# Debug-Edge_SWD-to-J-Link-Edu-Mini-adapte.net
KiCad netlist of a schematic drawn in EAGLE
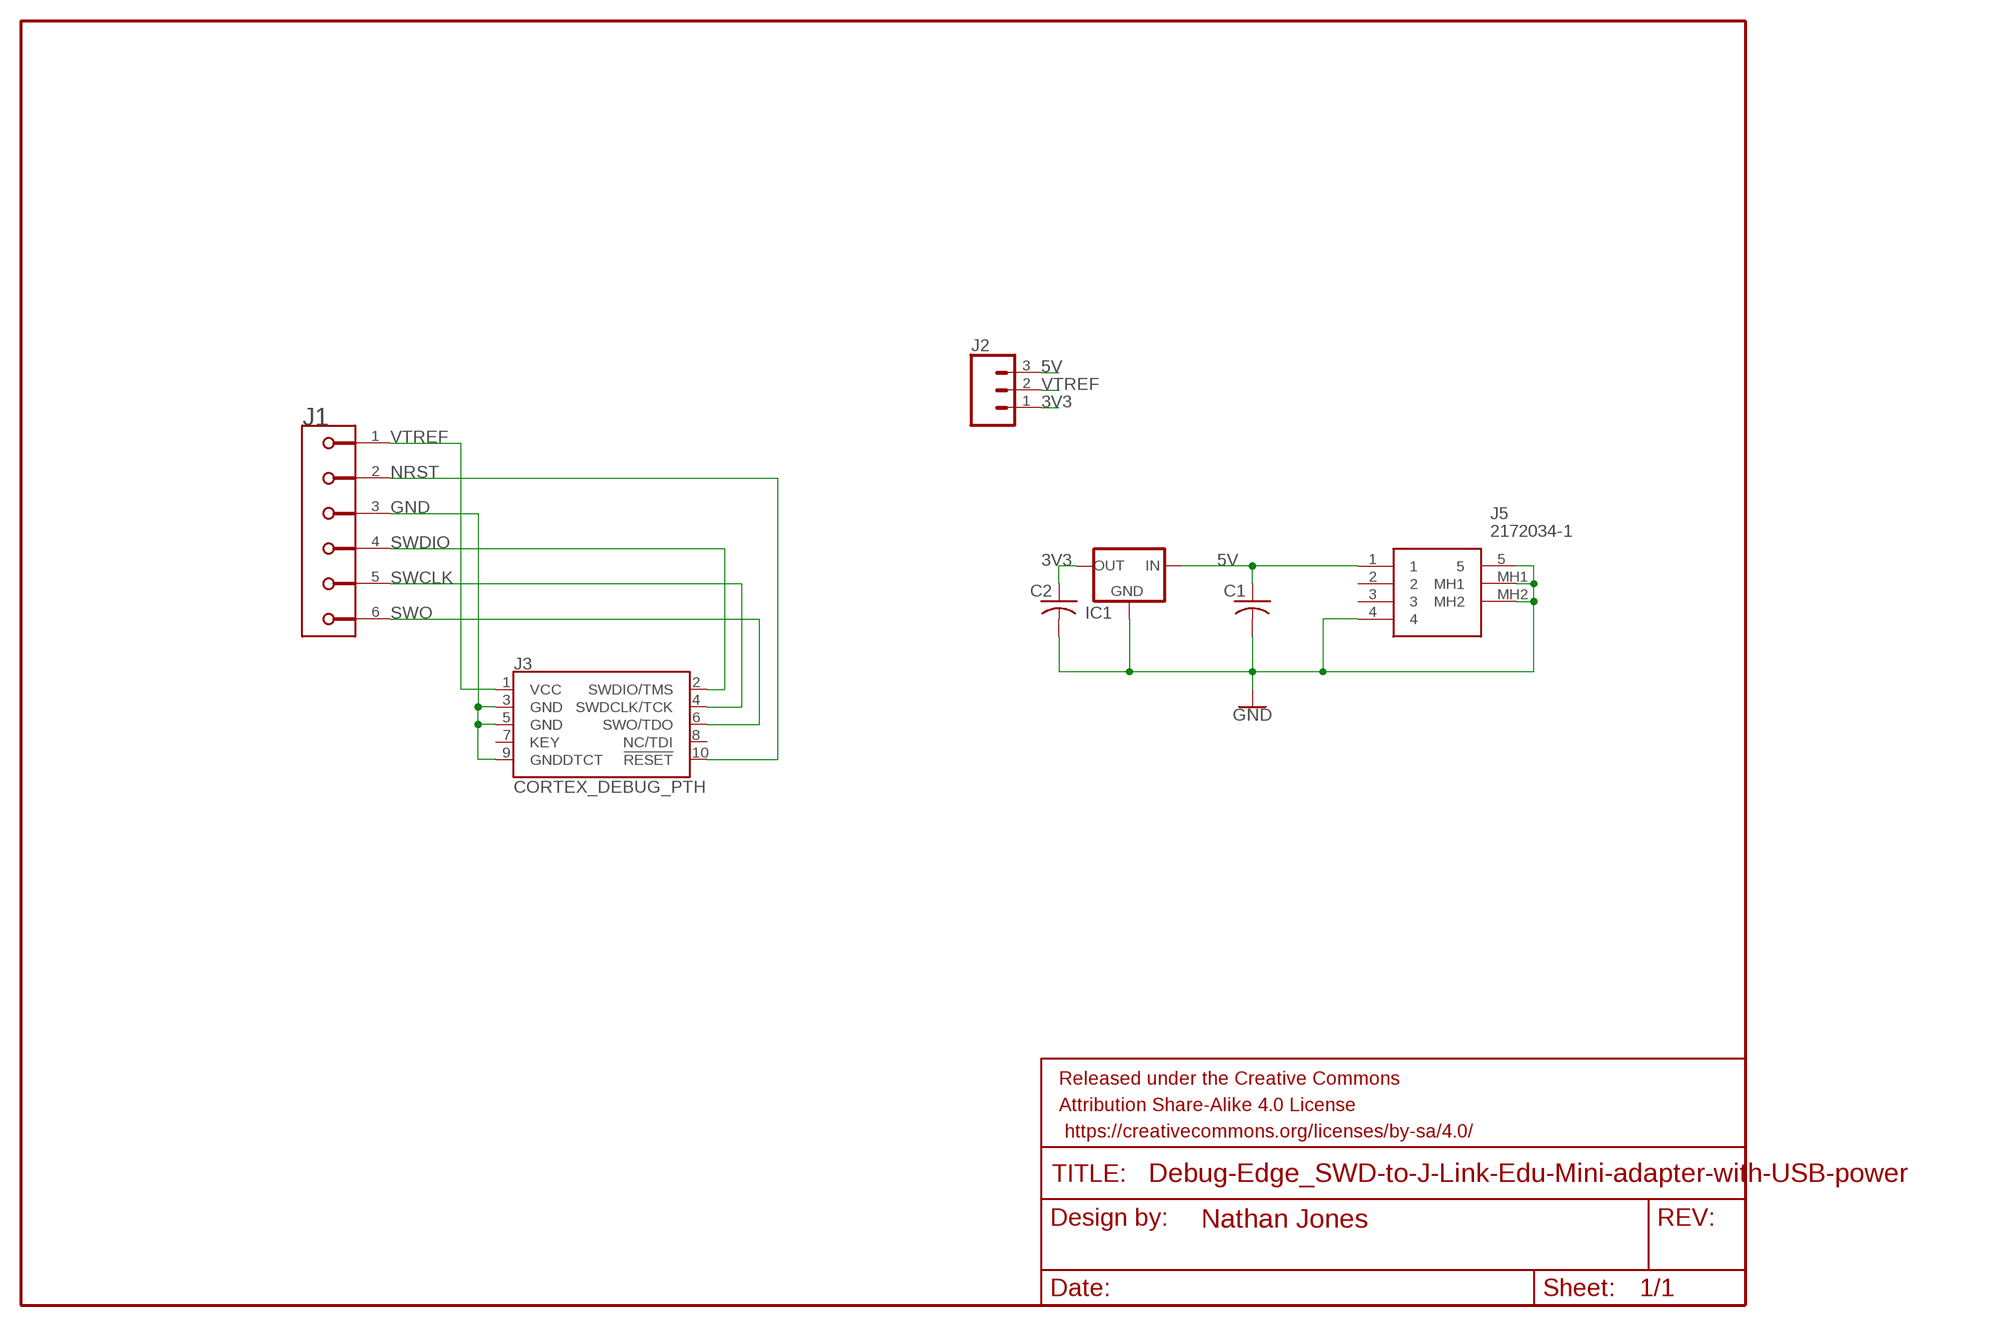
[diagram p0: schematic, sheet 1]

(export (version "E")
  (design (tool "Eeschema 10.0.6"))
  (components
    (comp (ref "C1")
      (value "C-US025-024X044")
      (footprint "eagle-import:C025-024X044")
      (libsource (lib "eagle-import") (part "C-US025-024X044"))
    )
    (comp (ref "C2")
      (value "C-US025-024X044")
      (footprint "eagle-import:C025-024X044")
      (libsource (lib "eagle-import") (part "C-US025-024X044"))
    )
    (comp (ref "FRAME1")
      (value "FRAME-LETTERNO_PACKAGE")
      (footprint "eagle-import:DUMMY")
      (fields (field (name "DESIGNER") "Nathan Jones") (field (name "DESIGNER_1") "Nathan Jones"))
      (libsource (lib "eagle-import") (part "FRAME-LETTERNO_PACKAGE"))
    )
    (comp (ref "IC1")
      (value "MCP1700INLINE")
      (footprint "eagle-import:TO92-INLINE")
      (libsource (lib "eagle-import") (part "MCP1700INLINE"))
    )
    (comp (ref "J1")
      (value "AVX_6-PIN_009159006061916")
      (footprint "eagle-import:AVX_6-PIN_009159006061916_0")
      (libsource (lib "eagle-import") (part "AVX_6-PIN_009159006061916"))
    )
    (comp (ref "J2")
      (value "CONN_031X03_NO_SILK")
      (footprint "eagle-import:1X03_NO_SILK")
      (libsource (lib "eagle-import") (part "CONN_031X03_NO_SILK"))
    )
    (comp (ref "J3")
      (value "CORTEX_DEBUG_PTH")
      (footprint "eagle-import:2X5-PTH-1.27MM")
      (libsource (lib "eagle-import") (part "CORTEX_DEBUG_PTH"))
    )
    (comp (ref "J5")
      (value "2172034-1")
      (footprint "eagle-import:21720341")
      (fields (field (name "MOUSER_PART_NUMBER") "571-2172034-1"))
      (libsource (lib "eagle-import") (part "2172034-1"))
    )
  )
  (nets
    (net (code "1") (name "/3V3") (class "Default")
      (node (ref "C2") (pin "1") (pinfunction "1_1") (pintype "passive"))
      (node (ref "IC1") (pin "3") (pinfunction "OUT_3") (pintype "passive"))
      (node (ref "J2") (pin "1") (pinfunction "1_1") (pintype "passive"))
    )
    (net (code "2") (name "/5V") (class "Default")
      (node (ref "C1") (pin "1") (pinfunction "1_1") (pintype "passive"))
      (node (ref "IC1") (pin "2") (pinfunction "IN_2") (pintype "input"))
      (node (ref "J2") (pin "3") (pinfunction "3_3") (pintype "passive"))
      (node (ref "J5") (pin "1") (pinfunction "1_1") (pintype "bidirectional"))
    )
    (net (code "3") (name "/NRST") (class "Default")
      (node (ref "J1") (pin "2") (pinfunction "2_2") (pintype "bidirectional"))
      (node (ref "J3") (pin "10") (pinfunction "~{RESET}_10") (pintype "bidirectional"))
    )
    (net (code "4") (name "/SWCLK") (class "Default")
      (node (ref "J1") (pin "5") (pinfunction "5_5") (pintype "bidirectional"))
      (node (ref "J3") (pin "4") (pinfunction "SWDCLK/TCK_4") (pintype "bidirectional"))
    )
    (net (code "5") (name "/SWDIO") (class "Default")
      (node (ref "J1") (pin "4") (pinfunction "4_4") (pintype "bidirectional"))
      (node (ref "J3") (pin "2") (pinfunction "SWDIO/TMS_2") (pintype "bidirectional"))
    )
    (net (code "6") (name "/SWO") (class "Default")
      (node (ref "J1") (pin "6") (pinfunction "6_6") (pintype "bidirectional"))
      (node (ref "J3") (pin "6") (pinfunction "SWO/TDO_6") (pintype "bidirectional"))
    )
    (net (code "7") (name "/VTREF") (class "Default")
      (node (ref "J1") (pin "1") (pinfunction "1_1") (pintype "bidirectional"))
      (node (ref "J2") (pin "2") (pinfunction "2_2") (pintype "passive"))
      (node (ref "J3") (pin "1") (pinfunction "VCC_1") (pintype "bidirectional"))
    )
    (net (code "8") (name "GND") (class "Default")
      (node (ref "C1") (pin "2") (pinfunction "2_2") (pintype "passive"))
      (node (ref "C2") (pin "2") (pinfunction "2_2") (pintype "passive"))
      (node (ref "IC1") (pin "1") (pinfunction "GND_1") (pintype "input"))
      (node (ref "J1") (pin "3") (pinfunction "3_3") (pintype "bidirectional"))
      (node (ref "J3") (pin "3") (pinfunction "GND_3") (pintype "bidirectional"))
      (node (ref "J3") (pin "5") (pinfunction "GND_5") (pintype "bidirectional"))
      (node (ref "J3") (pin "9") (pinfunction "GNDDTCT_9") (pintype "bidirectional"))
      (node (ref "J5") (pin "4") (pinfunction "4_4") (pintype "bidirectional"))
      (node (ref "J5") (pin "5") (pinfunction "5_5") (pintype "bidirectional"))
      (node (ref "J5") (pin "MH1") (pinfunction "MH1_MH1") (pintype "bidirectional"))
      (node (ref "J5") (pin "MH2") (pinfunction "MH2_MH2") (pintype "bidirectional"))
    )
    (net (code "9") (name "unconnected-(J3-KEY-Pad7)") (class "Default")
      (node (ref "J3") (pin "7") (pinfunction "KEY_7") (pintype "bidirectional"))
    )
    (net (code "10") (name "unconnected-(J3-NC{slash}TDI-Pad8)") (class "Default")
      (node (ref "J3") (pin "8") (pinfunction "NC/TDI_8") (pintype "bidirectional"))
    )
    (net (code "11") (name "unconnected-(J5-Pad2)") (class "Default")
      (node (ref "J5") (pin "2") (pinfunction "2_2") (pintype "bidirectional"))
    )
    (net (code "12") (name "unconnected-(J5-Pad3)") (class "Default")
      (node (ref "J5") (pin "3") (pinfunction "3_3") (pintype "bidirectional"))
    )
  )
)
